# Motor.net
KiCad netlist of a schematic drawn in Altium Designer
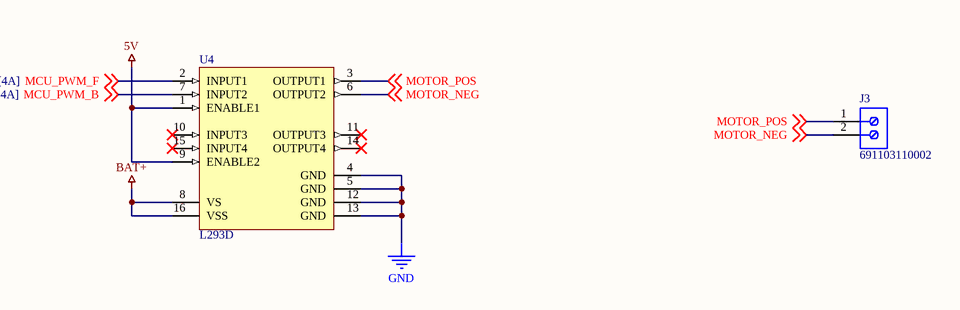
[diagram p0: Motor.SchDoc]

(export (version "E")
  (design (tool "Eeschema 10.0.6"))
  (components
    (comp (ref "J3")
      (value "691103110002")
      (footprint "691103110002")
      (fields (field (name "VOLTAGE") "125V"))
      (libsource (lib "Altium Content Vault") (part "TBL - 1R - 02P - Screw"))
    )
    (comp (ref "U4")
      (value "L293D")
      (footprint "STM-L293D-16")
      (description "Push-Pull Four Channel Driver with Diode, 4.5 to 36 V, -40 to 150 degC, 16-Pin PDIP, RoHS, Tube")
      (fields (field (name "MANUFACTURER") "STMicroelectronics"))
      (libsource (lib "Altium Content Vault") (part "STM-L293D-16"))
    )
  )
  (nets
    (net (code "1") (name "5V") (class "Default")
      (node (ref "U4") (pin "1") (pinfunction "ENABLE1_1") (pintype "input"))
      (node (ref "U4") (pin "9") (pinfunction "ENABLE2_9") (pintype "input"))
    )
    (net (code "2") (name "BAT+") (class "Default")
      (node (ref "U4") (pin "16") (pinfunction "VSS_16") (pintype "power_in"))
      (node (ref "U4") (pin "8") (pinfunction "VS_8") (pintype "power_in"))
    )
    (net (code "3") (name "GND") (class "Default")
      (node (ref "U4") (pin "12") (pinfunction "GND_12") (pintype "power_in"))
      (node (ref "U4") (pin "13") (pinfunction "GND_13") (pintype "power_in"))
      (node (ref "U4") (pin "4") (pinfunction "GND_4") (pintype "power_in"))
      (node (ref "U4") (pin "5") (pinfunction "GND_5") (pintype "power_in"))
    )
    (net (code "4") (name "MCU_PWM_B") (class "Default")
      (node (ref "U4") (pin "7") (pinfunction "INPUT2_7") (pintype "input"))
    )
    (net (code "5") (name "MCU_PWM_F") (class "Default")
      (node (ref "U4") (pin "2") (pinfunction "INPUT1_2") (pintype "input"))
    )
    (net (code "6") (name "MOTOR_NEG") (class "Default")
      (node (ref "J3") (pin "2") (pinfunction "2_2") (pintype "passive"))
      (node (ref "U4") (pin "6") (pinfunction "OUTPUT2_6") (pintype "output"))
    )
    (net (code "7") (name "MOTOR_POS") (class "Default")
      (node (ref "J3") (pin "1") (pinfunction "1_1") (pintype "passive"))
      (node (ref "U4") (pin "3") (pinfunction "OUTPUT1_3") (pintype "output"))
    )
    (net (code "8") (name "unconnected-(U4-INPUT3-Pad10)") (class "Default")
      (node (ref "U4") (pin "10") (pinfunction "INPUT3_10") (pintype "input+no_connect"))
    )
    (net (code "9") (name "unconnected-(U4-INPUT4-Pad15)") (class "Default")
      (node (ref "U4") (pin "15") (pinfunction "INPUT4_15") (pintype "input+no_connect"))
    )
    (net (code "10") (name "unconnected-(U4-OUTPUT3-Pad11)") (class "Default")
      (node (ref "U4") (pin "11") (pinfunction "OUTPUT3_11") (pintype "output+no_connect"))
    )
    (net (code "11") (name "unconnected-(U4-OUTPUT4-Pad14)") (class "Default")
      (node (ref "U4") (pin "14") (pinfunction "OUTPUT4_14") (pintype "output+no_connect"))
    )
  )
)
